# FotoTr.net
KiCad netlist of a schematic drawn in EAGLE
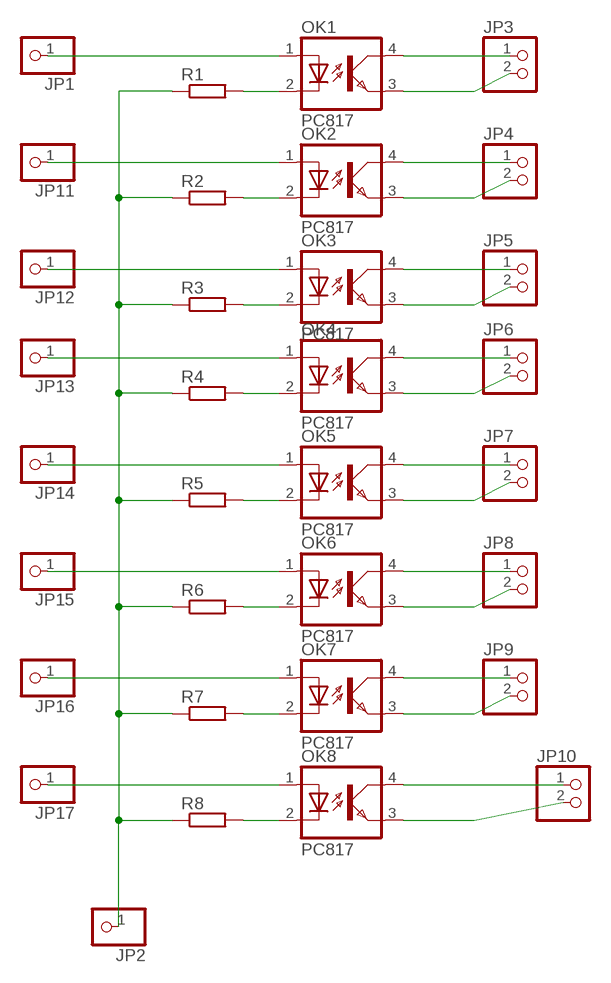
[diagram p0: schematic, sheet 1]

(export (version "E")
  (design (tool "Eeschema 10.0.6"))
  (components
    (comp (ref "JP1")
      (value "PINHD-1X1")
      (footprint "eagle-import:1X01")
      (libsource (lib "eagle-import") (part "PINHD-1X1"))
    )
    (comp (ref "JP2")
      (value "PINHD-1X1")
      (footprint "eagle-import:1X01")
      (libsource (lib "eagle-import") (part "PINHD-1X1"))
    )
    (comp (ref "JP3")
      (value "PINHD-1X2")
      (footprint "eagle-import:1X02")
      (libsource (lib "eagle-import") (part "PINHD-1X2"))
    )
    (comp (ref "JP4")
      (value "PINHD-1X2")
      (footprint "eagle-import:1X02")
      (libsource (lib "eagle-import") (part "PINHD-1X2"))
    )
    (comp (ref "JP5")
      (value "PINHD-1X2")
      (footprint "eagle-import:1X02")
      (libsource (lib "eagle-import") (part "PINHD-1X2"))
    )
    (comp (ref "JP6")
      (value "PINHD-1X2")
      (footprint "eagle-import:1X02")
      (libsource (lib "eagle-import") (part "PINHD-1X2"))
    )
    (comp (ref "JP7")
      (value "PINHD-1X2")
      (footprint "eagle-import:1X02")
      (libsource (lib "eagle-import") (part "PINHD-1X2"))
    )
    (comp (ref "JP8")
      (value "PINHD-1X2")
      (footprint "eagle-import:1X02")
      (libsource (lib "eagle-import") (part "PINHD-1X2"))
    )
    (comp (ref "JP9")
      (value "PINHD-1X2")
      (footprint "eagle-import:1X02")
      (libsource (lib "eagle-import") (part "PINHD-1X2"))
    )
    (comp (ref "JP10")
      (value "PINHD-1X2")
      (footprint "eagle-import:1X02")
      (libsource (lib "eagle-import") (part "PINHD-1X2"))
    )
    (comp (ref "JP11")
      (value "PINHD-1X1")
      (footprint "eagle-import:1X01")
      (libsource (lib "eagle-import") (part "PINHD-1X1"))
    )
    (comp (ref "JP12")
      (value "PINHD-1X1")
      (footprint "eagle-import:1X01")
      (libsource (lib "eagle-import") (part "PINHD-1X1"))
    )
    (comp (ref "JP13")
      (value "PINHD-1X1")
      (footprint "eagle-import:1X01")
      (libsource (lib "eagle-import") (part "PINHD-1X1"))
    )
    (comp (ref "JP14")
      (value "PINHD-1X1")
      (footprint "eagle-import:1X01")
      (libsource (lib "eagle-import") (part "PINHD-1X1"))
    )
    (comp (ref "JP15")
      (value "PINHD-1X1")
      (footprint "eagle-import:1X01")
      (libsource (lib "eagle-import") (part "PINHD-1X1"))
    )
    (comp (ref "JP16")
      (value "PINHD-1X1")
      (footprint "eagle-import:1X01")
      (libsource (lib "eagle-import") (part "PINHD-1X1"))
    )
    (comp (ref "JP17")
      (value "PINHD-1X1")
      (footprint "eagle-import:1X01")
      (libsource (lib "eagle-import") (part "PINHD-1X1"))
    )
    (comp (ref "OK1")
      (value "PC817")
      (footprint "eagle-import:DIL04")
      (fields (field (name "MPN") "PC817X4J000F"))
      (libsource (lib "eagle-import") (part "PC817"))
    )
    (comp (ref "OK2")
      (value "PC817")
      (footprint "eagle-import:DIL04")
      (fields (field (name "MPN") "PC817X4J000F"))
      (libsource (lib "eagle-import") (part "PC817"))
    )
    (comp (ref "OK3")
      (value "PC817")
      (footprint "eagle-import:DIL04")
      (fields (field (name "MPN") "PC817X4J000F"))
      (libsource (lib "eagle-import") (part "PC817"))
    )
    (comp (ref "OK4")
      (value "PC817")
      (footprint "eagle-import:DIL04")
      (fields (field (name "MPN") "PC817X4J000F"))
      (libsource (lib "eagle-import") (part "PC817"))
    )
    (comp (ref "OK5")
      (value "PC817")
      (footprint "eagle-import:DIL04")
      (fields (field (name "MPN") "PC817X4J000F"))
      (libsource (lib "eagle-import") (part "PC817"))
    )
    (comp (ref "OK6")
      (value "PC817")
      (footprint "eagle-import:DIL04")
      (fields (field (name "MPN") "PC817X4J000F"))
      (libsource (lib "eagle-import") (part "PC817"))
    )
    (comp (ref "OK7")
      (value "PC817")
      (footprint "eagle-import:DIL04")
      (fields (field (name "MPN") "PC817X4J000F"))
      (libsource (lib "eagle-import") (part "PC817"))
    )
    (comp (ref "OK8")
      (value "PC817")
      (footprint "eagle-import:DIL04")
      (fields (field (name "MPN") "PC817X4J000F"))
      (libsource (lib "eagle-import") (part "PC817"))
    )
    (comp (ref "R1")
      (value "R-EU_0204/2V")
      (footprint "eagle-import:0204V")
      (libsource (lib "eagle-import") (part "R-EU_0204/2V"))
    )
    (comp (ref "R2")
      (value "R-EU_0204/2V")
      (footprint "eagle-import:0204V")
      (libsource (lib "eagle-import") (part "R-EU_0204/2V"))
    )
    (comp (ref "R3")
      (value "R-EU_0204/2V")
      (footprint "eagle-import:0204V")
      (libsource (lib "eagle-import") (part "R-EU_0204/2V"))
    )
    (comp (ref "R4")
      (value "R-EU_0204/2V")
      (footprint "eagle-import:0204V")
      (libsource (lib "eagle-import") (part "R-EU_0204/2V"))
    )
    (comp (ref "R5")
      (value "R-EU_0204/2V")
      (footprint "eagle-import:0204V")
      (libsource (lib "eagle-import") (part "R-EU_0204/2V"))
    )
    (comp (ref "R6")
      (value "R-EU_0204/2V")
      (footprint "eagle-import:0204V")
      (libsource (lib "eagle-import") (part "R-EU_0204/2V"))
    )
    (comp (ref "R7")
      (value "R-EU_0204/2V")
      (footprint "eagle-import:0204V")
      (libsource (lib "eagle-import") (part "R-EU_0204/2V"))
    )
    (comp (ref "R8")
      (value "R-EU_0204/2V")
      (footprint "eagle-import:0204V")
      (libsource (lib "eagle-import") (part "R-EU_0204/2V"))
    )
  )
  (nets
    (net (code "1") (name "Net-(JP2-Pad1)") (class "Default")
      (node (ref "JP2") (pin "1") (pinfunction "1_1") (pintype "passive"))
      (node (ref "R1") (pin "1") (pinfunction "1_1") (pintype "passive"))
      (node (ref "R2") (pin "1") (pinfunction "1_1") (pintype "passive"))
      (node (ref "R3") (pin "1") (pinfunction "1_1") (pintype "passive"))
      (node (ref "R4") (pin "1") (pinfunction "1_1") (pintype "passive"))
      (node (ref "R5") (pin "1") (pinfunction "1_1") (pintype "passive"))
      (node (ref "R6") (pin "1") (pinfunction "1_1") (pintype "passive"))
      (node (ref "R7") (pin "1") (pinfunction "1_1") (pintype "passive"))
      (node (ref "R8") (pin "1") (pinfunction "1_1") (pintype "passive"))
    )
    (net (code "2") (name "Net-(OK1-A)") (class "Default")
      (node (ref "JP1") (pin "1") (pinfunction "1_1") (pintype "passive"))
      (node (ref "OK1") (pin "1") (pinfunction "A_1") (pintype "passive"))
    )
    (net (code "3") (name "Net-(OK1-C)") (class "Default")
      (node (ref "OK1") (pin "2") (pinfunction "C_2") (pintype "passive"))
      (node (ref "R1") (pin "2") (pinfunction "2_2") (pintype "passive"))
    )
    (net (code "4") (name "Net-(OK1-COL)") (class "Default")
      (node (ref "JP3") (pin "1") (pinfunction "1_1") (pintype "passive"))
      (node (ref "OK1") (pin "4") (pinfunction "COL_4") (pintype "passive"))
    )
    (net (code "5") (name "Net-(OK1-EMIT)") (class "Default")
      (node (ref "JP3") (pin "2") (pinfunction "2_2") (pintype "passive"))
      (node (ref "OK1") (pin "3") (pinfunction "EMIT_3") (pintype "passive"))
    )
    (net (code "6") (name "Net-(OK2-A)") (class "Default")
      (node (ref "JP11") (pin "1") (pinfunction "1_1") (pintype "passive"))
      (node (ref "OK2") (pin "1") (pinfunction "A_1") (pintype "passive"))
    )
    (net (code "7") (name "Net-(OK2-C)") (class "Default")
      (node (ref "OK2") (pin "2") (pinfunction "C_2") (pintype "passive"))
      (node (ref "R2") (pin "2") (pinfunction "2_2") (pintype "passive"))
    )
    (net (code "8") (name "Net-(OK2-COL)") (class "Default")
      (node (ref "JP4") (pin "1") (pinfunction "1_1") (pintype "passive"))
      (node (ref "OK2") (pin "4") (pinfunction "COL_4") (pintype "passive"))
    )
    (net (code "9") (name "Net-(OK2-EMIT)") (class "Default")
      (node (ref "JP4") (pin "2") (pinfunction "2_2") (pintype "passive"))
      (node (ref "OK2") (pin "3") (pinfunction "EMIT_3") (pintype "passive"))
    )
    (net (code "10") (name "Net-(OK3-A)") (class "Default")
      (node (ref "JP12") (pin "1") (pinfunction "1_1") (pintype "passive"))
      (node (ref "OK3") (pin "1") (pinfunction "A_1") (pintype "passive"))
    )
    (net (code "11") (name "Net-(OK3-C)") (class "Default")
      (node (ref "OK3") (pin "2") (pinfunction "C_2") (pintype "passive"))
      (node (ref "R3") (pin "2") (pinfunction "2_2") (pintype "passive"))
    )
    (net (code "12") (name "Net-(OK3-COL)") (class "Default")
      (node (ref "JP5") (pin "1") (pinfunction "1_1") (pintype "passive"))
      (node (ref "OK3") (pin "4") (pinfunction "COL_4") (pintype "passive"))
    )
    (net (code "13") (name "Net-(OK3-EMIT)") (class "Default")
      (node (ref "JP5") (pin "2") (pinfunction "2_2") (pintype "passive"))
      (node (ref "OK3") (pin "3") (pinfunction "EMIT_3") (pintype "passive"))
    )
    (net (code "14") (name "Net-(OK4-A)") (class "Default")
      (node (ref "JP13") (pin "1") (pinfunction "1_1") (pintype "passive"))
      (node (ref "OK4") (pin "1") (pinfunction "A_1") (pintype "passive"))
    )
    (net (code "15") (name "Net-(OK4-C)") (class "Default")
      (node (ref "OK4") (pin "2") (pinfunction "C_2") (pintype "passive"))
      (node (ref "R4") (pin "2") (pinfunction "2_2") (pintype "passive"))
    )
    (net (code "16") (name "Net-(OK4-COL)") (class "Default")
      (node (ref "JP6") (pin "1") (pinfunction "1_1") (pintype "passive"))
      (node (ref "OK4") (pin "4") (pinfunction "COL_4") (pintype "passive"))
    )
    (net (code "17") (name "Net-(OK4-EMIT)") (class "Default")
      (node (ref "JP6") (pin "2") (pinfunction "2_2") (pintype "passive"))
      (node (ref "OK4") (pin "3") (pinfunction "EMIT_3") (pintype "passive"))
    )
    (net (code "18") (name "Net-(OK5-A)") (class "Default")
      (node (ref "JP14") (pin "1") (pinfunction "1_1") (pintype "passive"))
      (node (ref "OK5") (pin "1") (pinfunction "A_1") (pintype "passive"))
    )
    (net (code "19") (name "Net-(OK5-C)") (class "Default")
      (node (ref "OK5") (pin "2") (pinfunction "C_2") (pintype "passive"))
      (node (ref "R5") (pin "2") (pinfunction "2_2") (pintype "passive"))
    )
    (net (code "20") (name "Net-(OK5-COL)") (class "Default")
      (node (ref "JP7") (pin "1") (pinfunction "1_1") (pintype "passive"))
      (node (ref "OK5") (pin "4") (pinfunction "COL_4") (pintype "passive"))
    )
    (net (code "21") (name "Net-(OK5-EMIT)") (class "Default")
      (node (ref "JP7") (pin "2") (pinfunction "2_2") (pintype "passive"))
      (node (ref "OK5") (pin "3") (pinfunction "EMIT_3") (pintype "passive"))
    )
    (net (code "22") (name "Net-(OK6-A)") (class "Default")
      (node (ref "JP15") (pin "1") (pinfunction "1_1") (pintype "passive"))
      (node (ref "OK6") (pin "1") (pinfunction "A_1") (pintype "passive"))
    )
    (net (code "23") (name "Net-(OK6-C)") (class "Default")
      (node (ref "OK6") (pin "2") (pinfunction "C_2") (pintype "passive"))
      (node (ref "R6") (pin "2") (pinfunction "2_2") (pintype "passive"))
    )
    (net (code "24") (name "Net-(OK6-COL)") (class "Default")
      (node (ref "JP8") (pin "1") (pinfunction "1_1") (pintype "passive"))
      (node (ref "OK6") (pin "4") (pinfunction "COL_4") (pintype "passive"))
    )
    (net (code "25") (name "Net-(OK6-EMIT)") (class "Default")
      (node (ref "JP8") (pin "2") (pinfunction "2_2") (pintype "passive"))
      (node (ref "OK6") (pin "3") (pinfunction "EMIT_3") (pintype "passive"))
    )
    (net (code "26") (name "Net-(OK7-A)") (class "Default")
      (node (ref "JP16") (pin "1") (pinfunction "1_1") (pintype "passive"))
      (node (ref "OK7") (pin "1") (pinfunction "A_1") (pintype "passive"))
    )
    (net (code "27") (name "Net-(OK7-C)") (class "Default")
      (node (ref "OK7") (pin "2") (pinfunction "C_2") (pintype "passive"))
      (node (ref "R7") (pin "2") (pinfunction "2_2") (pintype "passive"))
    )
    (net (code "28") (name "Net-(OK7-COL)") (class "Default")
      (node (ref "JP9") (pin "1") (pinfunction "1_1") (pintype "passive"))
      (node (ref "OK7") (pin "4") (pinfunction "COL_4") (pintype "passive"))
    )
    (net (code "29") (name "Net-(OK7-EMIT)") (class "Default")
      (node (ref "JP9") (pin "2") (pinfunction "2_2") (pintype "passive"))
      (node (ref "OK7") (pin "3") (pinfunction "EMIT_3") (pintype "passive"))
    )
    (net (code "30") (name "Net-(OK8-A)") (class "Default")
      (node (ref "JP17") (pin "1") (pinfunction "1_1") (pintype "passive"))
      (node (ref "OK8") (pin "1") (pinfunction "A_1") (pintype "passive"))
    )
    (net (code "31") (name "Net-(OK8-C)") (class "Default")
      (node (ref "OK8") (pin "2") (pinfunction "C_2") (pintype "passive"))
      (node (ref "R8") (pin "2") (pinfunction "2_2") (pintype "passive"))
    )
    (net (code "32") (name "Net-(OK8-COL)") (class "Default")
      (node (ref "JP10") (pin "1") (pinfunction "1_1") (pintype "passive"))
      (node (ref "OK8") (pin "4") (pinfunction "COL_4") (pintype "passive"))
    )
    (net (code "33") (name "Net-(OK8-EMIT)") (class "Default")
      (node (ref "JP10") (pin "2") (pinfunction "2_2") (pintype "passive"))
      (node (ref "OK8") (pin "3") (pinfunction "EMIT_3") (pintype "passive"))
    )
  )
)
